# Nabila.net
KiCad netlist of a schematic drawn in EAGLE
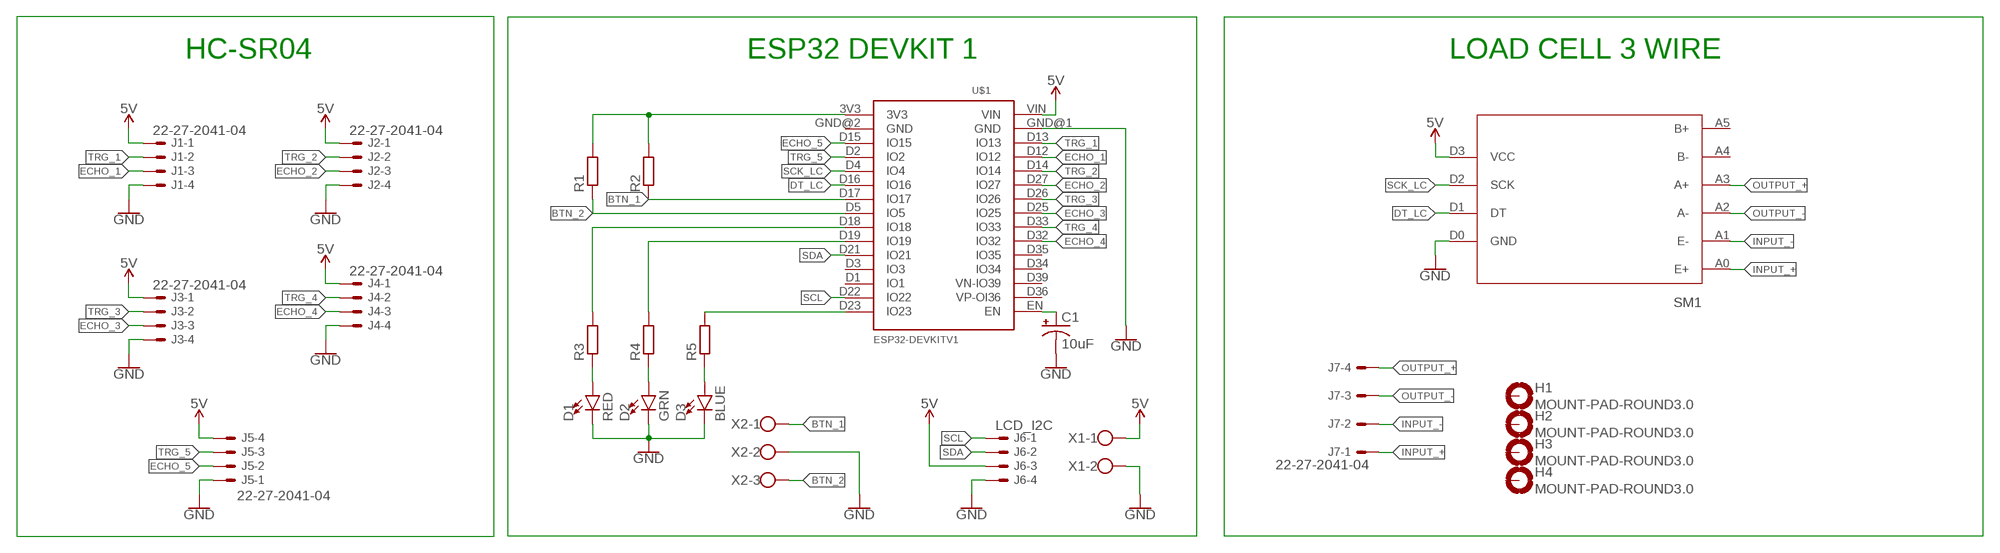
[diagram p0: schematic, sheet 1]

(export (version "E")
  (design (tool "Eeschema 10.0.6"))
  (components
    (comp (ref "C1")
      (value "10uF")
      (footprint "eagle-import:E2-5")
      (libsource (lib "eagle-import") (part "CPOL-USE2-5"))
    )
    (comp (ref "D1")
      (value "RED")
      (footprint "eagle-import:LED_5MM")
      (libsource (lib "eagle-import") (part "LED5MM"))
    )
    (comp (ref "D2")
      (value "GRN")
      (footprint "eagle-import:LED_5MM")
      (libsource (lib "eagle-import") (part "LED5MM"))
    )
    (comp (ref "D3")
      (value "BLUE")
      (footprint "eagle-import:LED_5MM")
      (libsource (lib "eagle-import") (part "LED5MM"))
    )
    (comp (ref "H1")
      (value "MOUNT-PAD-ROUND3.0")
      (footprint "eagle-import:3,0-PAD")
      (libsource (lib "eagle-import") (part "MOUNT-PAD-ROUND3.0"))
    )
    (comp (ref "H2")
      (value "MOUNT-PAD-ROUND3.0")
      (footprint "eagle-import:3,0-PAD")
      (libsource (lib "eagle-import") (part "MOUNT-PAD-ROUND3.0"))
    )
    (comp (ref "H3")
      (value "MOUNT-PAD-ROUND3.0")
      (footprint "eagle-import:3,0-PAD")
      (libsource (lib "eagle-import") (part "MOUNT-PAD-ROUND3.0"))
    )
    (comp (ref "H4")
      (value "MOUNT-PAD-ROUND3.0")
      (footprint "eagle-import:3,0-PAD")
      (libsource (lib "eagle-import") (part "MOUNT-PAD-ROUND3.0"))
    )
    (comp (ref "J1")
      (value "22-27-2041-04")
      (footprint "eagle-import:6410-04")
      (fields (field (name "MF") "MOLEX"))
      (libsource (lib "eagle-import") (part "22-?-0427-2041"))
    )
    (comp (ref "J2")
      (value "22-27-2041-04")
      (footprint "eagle-import:6410-04")
      (fields (field (name "MF") "MOLEX"))
      (libsource (lib "eagle-import") (part "22-?-0427-2041"))
    )
    (comp (ref "J3")
      (value "22-27-2041-04")
      (footprint "eagle-import:6410-04")
      (fields (field (name "MF") "MOLEX"))
      (libsource (lib "eagle-import") (part "22-?-0427-2041"))
    )
    (comp (ref "J4")
      (value "22-27-2041-04")
      (footprint "eagle-import:6410-04")
      (fields (field (name "MF") "MOLEX"))
      (libsource (lib "eagle-import") (part "22-?-0427-2041"))
    )
    (comp (ref "J5")
      (value "22-27-2041-04")
      (footprint "eagle-import:6410-04")
      (fields (field (name "MF") "MOLEX"))
      (libsource (lib "eagle-import") (part "22-?-0427-2041"))
    )
    (comp (ref "J6")
      (value "LCD_I2C")
      (footprint "eagle-import:6410-04")
      (fields (field (name "MF") "MOLEX"))
      (libsource (lib "eagle-import") (part "22-?-0427-2041"))
    )
    (comp (ref "J7")
      (value "22-27-2041-04")
      (footprint "eagle-import:6410-04")
      (fields (field (name "MF") "MOLEX"))
      (libsource (lib "eagle-import") (part "22-?-0427-2041"))
    )
    (comp (ref "R1")
      (value "R-EU_0207/10")
      (footprint "eagle-import:0207_10")
      (libsource (lib "eagle-import") (part "R-EU_0207/10"))
    )
    (comp (ref "R2")
      (value "R-EU_0207/10")
      (footprint "eagle-import:0207_10")
      (libsource (lib "eagle-import") (part "R-EU_0207/10"))
    )
    (comp (ref "R3")
      (value "R-EU_0207/10")
      (footprint "eagle-import:0207_10")
      (libsource (lib "eagle-import") (part "R-EU_0207/10"))
    )
    (comp (ref "R4")
      (value "R-EU_0207/10")
      (footprint "eagle-import:0207_10")
      (libsource (lib "eagle-import") (part "R-EU_0207/10"))
    )
    (comp (ref "R5")
      (value "R-EU_0207/10")
      (footprint "eagle-import:0207_10")
      (libsource (lib "eagle-import") (part "R-EU_0207/10"))
    )
    (comp (ref "SM1")
      (value "HX711")
      (footprint "eagle-import:HX711")
      (libsource (lib "eagle-import") (part "HX711"))
    )
    (comp (ref "U$1")
      (value "ESP32DEVKITV1")
      (footprint "eagle-import:ESP32-DEVKITV1")
      (libsource (lib "eagle-import") (part "ESP32DEVKITV1"))
    )
    (comp (ref "X1")
      (value "W237-102")
      (footprint "eagle-import:W237-102")
      (fields (field (name "MPN") "237-102"))
      (libsource (lib "eagle-import") (part "W237-102"))
    )
    (comp (ref "X2")
      (value "W237-103")
      (footprint "eagle-import:W237-103")
      (fields (field (name "MPN") "237-103"))
      (libsource (lib "eagle-import") (part "W237-103"))
    )
  )
  (nets
    (net (code "1") (name "5V") (class "Default")
      (node (ref "J1") (pin "1") (pinfunction "S_1") (pintype "passive"))
      (node (ref "J2") (pin "1") (pinfunction "S_1") (pintype "passive"))
      (node (ref "J3") (pin "1") (pinfunction "S_1") (pintype "passive"))
      (node (ref "J4") (pin "1") (pinfunction "S_1") (pintype "passive"))
      (node (ref "J5") (pin "4") (pinfunction "S_4") (pintype "passive"))
      (node (ref "J6") (pin "3") (pinfunction "S_3") (pintype "passive"))
      (node (ref "SM1") (pin "D3") (pinfunction "VCC_D3") (pintype "bidirectional"))
      (node (ref "U$1") (pin "VIN") (pinfunction "VIN_VIN") (pintype "bidirectional"))
      (node (ref "X1") (pin "1") (pinfunction "KL_1") (pintype "passive"))
    )
    (net (code "2") (name "BTN_1") (class "Default")
      (node (ref "R2") (pin "1") (pinfunction "1_1") (pintype "passive"))
      (node (ref "U$1") (pin "D17") (pinfunction "IO17_D17") (pintype "bidirectional"))
      (node (ref "X2") (pin "1") (pinfunction "KL_1") (pintype "passive"))
    )
    (net (code "3") (name "BTN_2") (class "Default")
      (node (ref "R1") (pin "1") (pinfunction "1_1") (pintype "passive"))
      (node (ref "U$1") (pin "D5") (pinfunction "IO5_D5") (pintype "bidirectional"))
      (node (ref "X2") (pin "3") (pinfunction "KL_3") (pintype "passive"))
    )
    (net (code "4") (name "DT_LC") (class "Default")
      (node (ref "SM1") (pin "D1") (pinfunction "DT_D1") (pintype "bidirectional"))
      (node (ref "U$1") (pin "D16") (pinfunction "IO16_D16") (pintype "bidirectional"))
    )
    (net (code "5") (name "ECHO_1") (class "Default")
      (node (ref "J1") (pin "3") (pinfunction "S_3") (pintype "passive"))
      (node (ref "U$1") (pin "D12") (pinfunction "IO12_D12") (pintype "bidirectional"))
    )
    (net (code "6") (name "ECHO_2") (class "Default")
      (node (ref "J2") (pin "3") (pinfunction "S_3") (pintype "passive"))
      (node (ref "U$1") (pin "D27") (pinfunction "IO27_D27") (pintype "bidirectional"))
    )
    (net (code "7") (name "ECHO_3") (class "Default")
      (node (ref "J3") (pin "3") (pinfunction "S_3") (pintype "passive"))
      (node (ref "U$1") (pin "D25") (pinfunction "IO25_D25") (pintype "bidirectional"))
    )
    (net (code "8") (name "ECHO_4") (class "Default")
      (node (ref "J4") (pin "3") (pinfunction "S_3") (pintype "passive"))
      (node (ref "U$1") (pin "D32") (pinfunction "IO32_D32") (pintype "bidirectional"))
    )
    (net (code "9") (name "ECHO_5") (class "Default")
      (node (ref "J5") (pin "2") (pinfunction "S_2") (pintype "passive"))
      (node (ref "U$1") (pin "D15") (pinfunction "IO15_D15") (pintype "bidirectional"))
    )
    (net (code "10") (name "GND") (class "Default")
      (node (ref "C1") (pin "-") (pinfunction "-_-") (pintype "passive"))
      (node (ref "D1") (pin "K") (pinfunction "C_K") (pintype "passive"))
      (node (ref "D2") (pin "K") (pinfunction "C_K") (pintype "passive"))
      (node (ref "D3") (pin "K") (pinfunction "C_K") (pintype "passive"))
      (node (ref "J1") (pin "4") (pinfunction "S_4") (pintype "passive"))
      (node (ref "J2") (pin "4") (pinfunction "S_4") (pintype "passive"))
      (node (ref "J3") (pin "4") (pinfunction "S_4") (pintype "passive"))
      (node (ref "J4") (pin "4") (pinfunction "S_4") (pintype "passive"))
      (node (ref "J5") (pin "1") (pinfunction "S_1") (pintype "passive"))
      (node (ref "J6") (pin "4") (pinfunction "S_4") (pintype "passive"))
      (node (ref "SM1") (pin "D0") (pinfunction "GND_D0") (pintype "bidirectional"))
      (node (ref "U$1") (pin "GND@1") (pinfunction "GND_GND@1") (pintype "bidirectional"))
      (node (ref "X1") (pin "2") (pinfunction "KL_2") (pintype "passive"))
      (node (ref "X2") (pin "2") (pinfunction "KL_2") (pintype "passive"))
    )
    (net (code "11") (name "INPUT_+") (class "Default")
      (node (ref "J7") (pin "1") (pinfunction "S_1") (pintype "passive"))
      (node (ref "SM1") (pin "A0") (pinfunction "E+_A0") (pintype "bidirectional"))
    )
    (net (code "12") (name "INPUT_-") (class "Default")
      (node (ref "J7") (pin "2") (pinfunction "S_2") (pintype "passive"))
      (node (ref "SM1") (pin "A1") (pinfunction "E-_A1") (pintype "bidirectional"))
    )
    (net (code "13") (name "Net-(C1-Pad+)") (class "Default")
      (node (ref "C1") (pin "+") (pinfunction "+_+") (pintype "passive"))
      (node (ref "U$1") (pin "EN") (pinfunction "EN_EN") (pintype "bidirectional"))
    )
    (net (code "14") (name "Net-(D1-PadA)") (class "Default")
      (node (ref "D1") (pin "A") (pinfunction "A_A") (pintype "passive"))
      (node (ref "R3") (pin "1") (pinfunction "1_1") (pintype "passive"))
    )
    (net (code "15") (name "Net-(D2-PadA)") (class "Default")
      (node (ref "D2") (pin "A") (pinfunction "A_A") (pintype "passive"))
      (node (ref "R4") (pin "1") (pinfunction "1_1") (pintype "passive"))
    )
    (net (code "16") (name "Net-(D3-PadA)") (class "Default")
      (node (ref "D3") (pin "A") (pinfunction "A_A") (pintype "passive"))
      (node (ref "R5") (pin "1") (pinfunction "1_1") (pintype "passive"))
    )
    (net (code "17") (name "Net-(R1-Pad2)") (class "Default")
      (node (ref "R1") (pin "2") (pinfunction "2_2") (pintype "passive"))
      (node (ref "R2") (pin "2") (pinfunction "2_2") (pintype "passive"))
      (node (ref "U$1") (pin "3V3") (pinfunction "3V3_3V3") (pintype "bidirectional"))
    )
    (net (code "18") (name "Net-(U$1-IO18)") (class "Default")
      (node (ref "R3") (pin "2") (pinfunction "2_2") (pintype "passive"))
      (node (ref "U$1") (pin "D18") (pinfunction "IO18_D18") (pintype "bidirectional"))
    )
    (net (code "19") (name "Net-(U$1-IO19)") (class "Default")
      (node (ref "R4") (pin "2") (pinfunction "2_2") (pintype "passive"))
      (node (ref "U$1") (pin "D19") (pinfunction "IO19_D19") (pintype "bidirectional"))
    )
    (net (code "20") (name "Net-(U$1-IO23)") (class "Default")
      (node (ref "R5") (pin "2") (pinfunction "2_2") (pintype "passive"))
      (node (ref "U$1") (pin "D23") (pinfunction "IO23_D23") (pintype "bidirectional"))
    )
    (net (code "21") (name "OUTPUT_+") (class "Default")
      (node (ref "J7") (pin "4") (pinfunction "S_4") (pintype "passive"))
      (node (ref "SM1") (pin "A3") (pinfunction "A+_A3") (pintype "bidirectional"))
    )
    (net (code "22") (name "OUTPUT_-") (class "Default")
      (node (ref "J7") (pin "3") (pinfunction "S_3") (pintype "passive"))
      (node (ref "SM1") (pin "A2") (pinfunction "A-_A2") (pintype "bidirectional"))
    )
    (net (code "23") (name "SCK_LC") (class "Default")
      (node (ref "SM1") (pin "D2") (pinfunction "SCK_D2") (pintype "bidirectional"))
      (node (ref "U$1") (pin "D4") (pinfunction "IO4_D4") (pintype "bidirectional"))
    )
    (net (code "24") (name "SCL") (class "Default")
      (node (ref "J6") (pin "1") (pinfunction "S_1") (pintype "passive"))
      (node (ref "U$1") (pin "D22") (pinfunction "IO22_D22") (pintype "bidirectional"))
    )
    (net (code "25") (name "SDA") (class "Default")
      (node (ref "J6") (pin "2") (pinfunction "S_2") (pintype "passive"))
      (node (ref "U$1") (pin "D21") (pinfunction "IO21_D21") (pintype "bidirectional"))
    )
    (net (code "26") (name "TRG_1") (class "Default")
      (node (ref "J1") (pin "2") (pinfunction "S_2") (pintype "passive"))
      (node (ref "U$1") (pin "D13") (pinfunction "IO13_D13") (pintype "bidirectional"))
    )
    (net (code "27") (name "TRG_2") (class "Default")
      (node (ref "J2") (pin "2") (pinfunction "S_2") (pintype "passive"))
      (node (ref "U$1") (pin "D14") (pinfunction "IO14_D14") (pintype "bidirectional"))
    )
    (net (code "28") (name "TRG_3") (class "Default")
      (node (ref "J3") (pin "2") (pinfunction "S_2") (pintype "passive"))
      (node (ref "U$1") (pin "D26") (pinfunction "IO26_D26") (pintype "bidirectional"))
    )
    (net (code "29") (name "TRG_4") (class "Default")
      (node (ref "J4") (pin "2") (pinfunction "S_2") (pintype "passive"))
      (node (ref "U$1") (pin "D33") (pinfunction "IO33_D33") (pintype "bidirectional"))
    )
    (net (code "30") (name "TRG_5") (class "Default")
      (node (ref "J5") (pin "3") (pinfunction "S_3") (pintype "passive"))
      (node (ref "U$1") (pin "D2") (pinfunction "IO2_D2") (pintype "bidirectional"))
    )
    (net (code "31") (name "unconnected-(H1-MOUNT-PadB3,0)") (class "Default")
      (node (ref "H1") (pin "B3,0") (pinfunction "MOUNT_B3,0") (pintype "passive"))
    )
    (net (code "32") (name "unconnected-(H2-MOUNT-PadB3,0)") (class "Default")
      (node (ref "H2") (pin "B3,0") (pinfunction "MOUNT_B3,0") (pintype "passive"))
    )
    (net (code "33") (name "unconnected-(H3-MOUNT-PadB3,0)") (class "Default")
      (node (ref "H3") (pin "B3,0") (pinfunction "MOUNT_B3,0") (pintype "passive"))
    )
    (net (code "34") (name "unconnected-(H4-MOUNT-PadB3,0)") (class "Default")
      (node (ref "H4") (pin "B3,0") (pinfunction "MOUNT_B3,0") (pintype "passive"))
    )
    (net (code "35") (name "unconnected-(SM1-B+-PadA5)") (class "Default")
      (node (ref "SM1") (pin "A5") (pinfunction "B+_A5") (pintype "bidirectional"))
    )
    (net (code "36") (name "unconnected-(SM1-B--PadA4)") (class "Default")
      (node (ref "SM1") (pin "A4") (pinfunction "B-_A4") (pintype "bidirectional"))
    )
    (net (code "37") (name "unconnected-(U$1-GND-PadGND@2)") (class "Default")
      (node (ref "U$1") (pin "GND@2") (pinfunction "GND_GND@2") (pintype "bidirectional"))
    )
    (net (code "38") (name "unconnected-(U$1-IO1-PadD1)") (class "Default")
      (node (ref "U$1") (pin "D1") (pinfunction "IO1_D1") (pintype "bidirectional"))
    )
    (net (code "39") (name "unconnected-(U$1-IO3-PadD3)") (class "Default")
      (node (ref "U$1") (pin "D3") (pinfunction "IO3_D3") (pintype "bidirectional"))
    )
    (net (code "40") (name "unconnected-(U$1-IO34-PadD34)") (class "Default")
      (node (ref "U$1") (pin "D34") (pinfunction "IO34_D34") (pintype "bidirectional"))
    )
    (net (code "41") (name "unconnected-(U$1-IO35-PadD35)") (class "Default")
      (node (ref "U$1") (pin "D35") (pinfunction "IO35_D35") (pintype "bidirectional"))
    )
    (net (code "42") (name "unconnected-(U$1-VN-IO39-PadD39)") (class "Default")
      (node (ref "U$1") (pin "D39") (pinfunction "VN-IO39_D39") (pintype "bidirectional"))
    )
    (net (code "43") (name "unconnected-(U$1-VP-OI36-PadD36)") (class "Default")
      (node (ref "U$1") (pin "D36") (pinfunction "VP-OI36_D36") (pintype "bidirectional"))
    )
  )
)
